# irledwafer.net
KiCad netlist of a schematic drawn in EAGLE
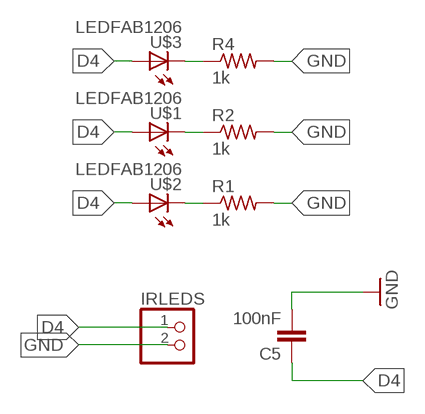
[diagram p0: schematic, sheet 1]

(export (version "E")
  (design (tool "Eeschema 10.0.6"))
  (components
    (comp (ref "C5")
      (value "100nF")
      (footprint "eagle-import:1206")
      (libsource (lib "eagle-import") (part "CAP1206"))
    )
    (comp (ref "IRLEDS")
      (value "PINHD-1X2")
      (footprint "eagle-import:1X02")
      (libsource (lib "eagle-import") (part "PINHD-1X2"))
    )
    (comp (ref "R1")
      (value "1k")
      (footprint "eagle-import:R1206FAB")
      (libsource (lib "eagle-import") (part "RES-US1206FAB"))
    )
    (comp (ref "R2")
      (value "1k")
      (footprint "eagle-import:R1206FAB")
      (libsource (lib "eagle-import") (part "RES-US1206FAB"))
    )
    (comp (ref "R4")
      (value "1k")
      (footprint "eagle-import:R1206FAB")
      (libsource (lib "eagle-import") (part "RES-US1206FAB"))
    )
    (comp (ref "U$1")
      (value "LEDFAB1206")
      (footprint "eagle-import:LED1206FAB")
      (libsource (lib "eagle-import") (part "LEDFAB1206"))
    )
    (comp (ref "U$2")
      (value "LEDFAB1206")
      (footprint "eagle-import:LED1206FAB")
      (libsource (lib "eagle-import") (part "LEDFAB1206"))
    )
    (comp (ref "U$3")
      (value "LEDFAB1206")
      (footprint "eagle-import:LED1206FAB")
      (libsource (lib "eagle-import") (part "LEDFAB1206"))
    )
  )
  (nets
    (net (code "1") (name "D4") (class "Default")
      (node (ref "C5") (pin "1") (pinfunction "1_1") (pintype "passive"))
      (node (ref "IRLEDS") (pin "1") (pinfunction "1_1") (pintype "passive"))
      (node (ref "U$1") (pin "1") (pinfunction "A_1") (pintype "passive"))
      (node (ref "U$2") (pin "1") (pinfunction "A_1") (pintype "passive"))
      (node (ref "U$3") (pin "1") (pinfunction "A_1") (pintype "passive"))
    )
    (net (code "2") (name "GND") (class "Default")
      (node (ref "C5") (pin "2") (pinfunction "2_2") (pintype "passive"))
      (node (ref "IRLEDS") (pin "2") (pinfunction "2_2") (pintype "passive"))
      (node (ref "R1") (pin "2") (pinfunction "2_2") (pintype "passive"))
      (node (ref "R2") (pin "2") (pinfunction "2_2") (pintype "passive"))
      (node (ref "R4") (pin "2") (pinfunction "2_2") (pintype "passive"))
    )
    (net (code "3") (name "Net-(U$1-C)") (class "Default")
      (node (ref "R2") (pin "1") (pinfunction "1_1") (pintype "passive"))
      (node (ref "U$1") (pin "2") (pinfunction "C_2") (pintype "passive"))
    )
    (net (code "4") (name "Net-(U$2-C)") (class "Default")
      (node (ref "R1") (pin "1") (pinfunction "1_1") (pintype "passive"))
      (node (ref "U$2") (pin "2") (pinfunction "C_2") (pintype "passive"))
    )
    (net (code "5") (name "Net-(U$3-C)") (class "Default")
      (node (ref "R4") (pin "1") (pinfunction "1_1") (pintype "passive"))
      (node (ref "U$3") (pin "2") (pinfunction "C_2") (pintype "passive"))
    )
  )
)
